# ATX_PSU_Breakout_Mini.net
KiCad netlist of a schematic drawn in EAGLE
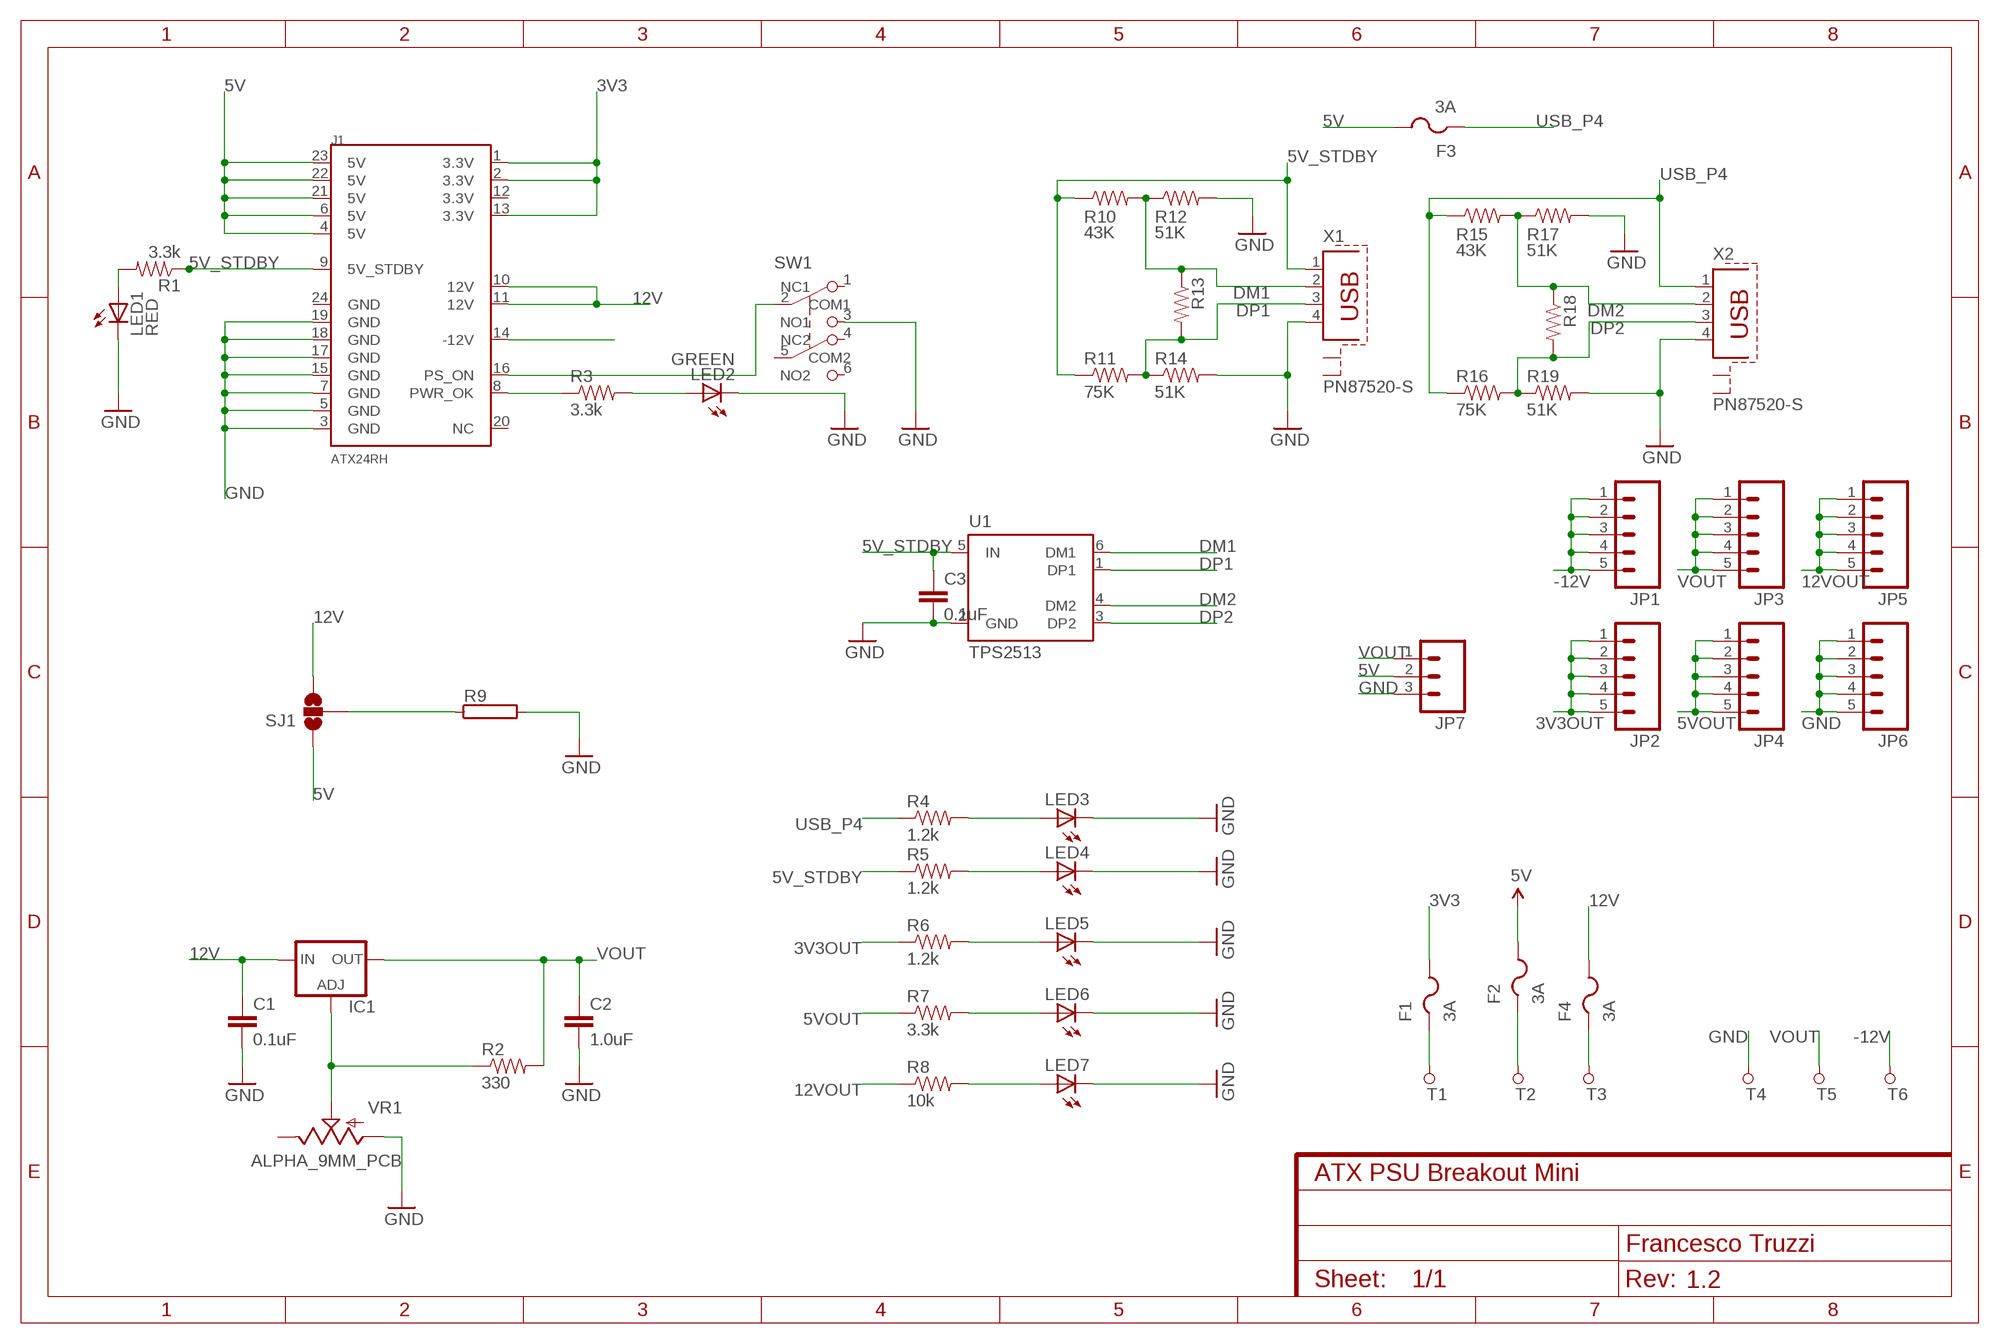
[diagram p0: schematic, sheet 1]

(export (version "E")
  (design (tool "Eeschema 10.0.6"))
  (components
    (comp (ref "C1")
      (value "0.1uF")
      (footprint "eagle-import:0805")
      (libsource (lib "eagle-import") (part "1.0UF-25V-+80/-20(0805)"))
    )
    (comp (ref "C2")
      (value "1.0uF")
      (footprint "eagle-import:0805")
      (libsource (lib "eagle-import") (part "1.0UF-25V-+80/-20(0805)"))
    )
    (comp (ref "C3")
      (value "0.1uF")
      (footprint "eagle-import:0805")
      (libsource (lib "eagle-import") (part "1.0UF-25V-+80/-20(0805)"))
    )
    (comp (ref "F1")
      (value "3A")
      (footprint "eagle-import:1812")
      (libsource (lib "eagle-import") (part "PTCFUSE-1812"))
    )
    (comp (ref "F2")
      (value "3A")
      (footprint "eagle-import:1812")
      (libsource (lib "eagle-import") (part "PTCFUSE-1812"))
    )
    (comp (ref "F3")
      (value "3A")
      (footprint "eagle-import:1812")
      (libsource (lib "eagle-import") (part "PTCFUSE-1812"))
    )
    (comp (ref "F4")
      (value "3A")
      (footprint "eagle-import:1812")
      (libsource (lib "eagle-import") (part "PTCFUSE-1812"))
    )
    (comp (ref "IC1")
      (value "LM317TL")
      (footprint "eagle-import:317TL")
      (libsource (lib "eagle-import") (part "LM317TL"))
    )
    (comp (ref "J1")
      (value "ATX24RH")
      (footprint "eagle-import:ATX24_RIGHT_ANGLE")
      (libsource (lib "eagle-import") (part "ATX24RH"))
    )
    (comp (ref "JP1")
      (value "M05PTH")
      (footprint "eagle-import:1X05")
      (libsource (lib "eagle-import") (part "M05PTH"))
    )
    (comp (ref "JP2")
      (value "M05PTH")
      (footprint "eagle-import:1X05")
      (libsource (lib "eagle-import") (part "M05PTH"))
    )
    (comp (ref "JP3")
      (value "M05PTH")
      (footprint "eagle-import:1X05")
      (libsource (lib "eagle-import") (part "M05PTH"))
    )
    (comp (ref "JP4")
      (value "M05PTH")
      (footprint "eagle-import:1X05")
      (libsource (lib "eagle-import") (part "M05PTH"))
    )
    (comp (ref "JP5")
      (value "M05PTH")
      (footprint "eagle-import:1X05")
      (libsource (lib "eagle-import") (part "M05PTH"))
    )
    (comp (ref "JP6")
      (value "M05PTH")
      (footprint "eagle-import:1X05")
      (libsource (lib "eagle-import") (part "M05PTH"))
    )
    (comp (ref "JP7")
      (value "M03LOCK")
      (footprint "eagle-import:1X03_LOCK")
      (libsource (lib "eagle-import") (part "M03LOCK"))
    )
    (comp (ref "LED1")
      (value "RED")
      (footprint "eagle-import:CHIPLED_0805")
      (libsource (lib "eagle-import") (part "LEDCHIPLED_0805"))
    )
    (comp (ref "LED2")
      (value "GREEN")
      (footprint "eagle-import:CHIPLED_0805")
      (libsource (lib "eagle-import") (part "LEDCHIPLED_0805"))
    )
    (comp (ref "LED3")
      (value "LEDCHIPLED_0805")
      (footprint "eagle-import:CHIPLED_0805")
      (libsource (lib "eagle-import") (part "LEDCHIPLED_0805"))
    )
    (comp (ref "LED4")
      (value "LEDCHIPLED_0805")
      (footprint "eagle-import:CHIPLED_0805")
      (libsource (lib "eagle-import") (part "LEDCHIPLED_0805"))
    )
    (comp (ref "LED5")
      (value "LEDCHIPLED_0805")
      (footprint "eagle-import:CHIPLED_0805")
      (libsource (lib "eagle-import") (part "LEDCHIPLED_0805"))
    )
    (comp (ref "LED6")
      (value "LEDCHIPLED_0805")
      (footprint "eagle-import:CHIPLED_0805")
      (libsource (lib "eagle-import") (part "LEDCHIPLED_0805"))
    )
    (comp (ref "LED7")
      (value "LEDCHIPLED_0805")
      (footprint "eagle-import:CHIPLED_0805")
      (libsource (lib "eagle-import") (part "LEDCHIPLED_0805"))
    )
    (comp (ref "R1")
      (value "3.3k")
      (footprint "eagle-import:0805")
      (libsource (lib "eagle-import") (part "RESISTOR0805-RES"))
    )
    (comp (ref "R2")
      (value "330")
      (footprint "eagle-import:0805")
      (libsource (lib "eagle-import") (part "RESISTOR0805-RES"))
    )
    (comp (ref "R3")
      (value "3.3k")
      (footprint "eagle-import:0805")
      (libsource (lib "eagle-import") (part "RESISTOR0805-RES"))
    )
    (comp (ref "R4")
      (value "1.2k")
      (footprint "eagle-import:0805")
      (libsource (lib "eagle-import") (part "RESISTOR0805-RES"))
    )
    (comp (ref "R5")
      (value "1.2k")
      (footprint "eagle-import:0805")
      (libsource (lib "eagle-import") (part "RESISTOR0805-RES"))
    )
    (comp (ref "R6")
      (value "1.2k")
      (footprint "eagle-import:0805")
      (libsource (lib "eagle-import") (part "RESISTOR0805-RES"))
    )
    (comp (ref "R7")
      (value "3.3k")
      (footprint "eagle-import:0805")
      (libsource (lib "eagle-import") (part "RESISTOR0805-RES"))
    )
    (comp (ref "R8")
      (value "10k")
      (footprint "eagle-import:0805")
      (libsource (lib "eagle-import") (part "RESISTOR0805-RES"))
    )
    (comp (ref "R9")
      (value "RKH214-8")
      (footprint "eagle-import:KH214-8")
      (libsource (lib "eagle-import") (part "RKH214-8"))
    )
    (comp (ref "R10")
      (value "43K")
      (footprint "eagle-import:0805")
      (libsource (lib "eagle-import") (part "RESISTOR0805-RES"))
    )
    (comp (ref "R11")
      (value "75K")
      (footprint "eagle-import:0805")
      (libsource (lib "eagle-import") (part "RESISTOR0805-RES"))
    )
    (comp (ref "R12")
      (value "51K")
      (footprint "eagle-import:0805")
      (libsource (lib "eagle-import") (part "RESISTOR0805-RES"))
    )
    (comp (ref "R13")
      (value "RESISTOR0805-RES")
      (footprint "eagle-import:0805")
      (libsource (lib "eagle-import") (part "RESISTOR0805-RES"))
    )
    (comp (ref "R14")
      (value "51K")
      (footprint "eagle-import:0805")
      (libsource (lib "eagle-import") (part "RESISTOR0805-RES"))
    )
    (comp (ref "R15")
      (value "43K")
      (footprint "eagle-import:0805")
      (libsource (lib "eagle-import") (part "RESISTOR0805-RES"))
    )
    (comp (ref "R16")
      (value "75K")
      (footprint "eagle-import:0805")
      (libsource (lib "eagle-import") (part "RESISTOR0805-RES"))
    )
    (comp (ref "R17")
      (value "51K")
      (footprint "eagle-import:0805")
      (libsource (lib "eagle-import") (part "RESISTOR0805-RES"))
    )
    (comp (ref "R18")
      (value "RESISTOR0805-RES")
      (footprint "eagle-import:0805")
      (libsource (lib "eagle-import") (part "RESISTOR0805-RES"))
    )
    (comp (ref "R19")
      (value "51K")
      (footprint "eagle-import:0805")
      (libsource (lib "eagle-import") (part "RESISTOR0805-RES"))
    )
    (comp (ref "SJ1")
      (value "SOLDERJUMPER_2WAYS")
      (footprint "eagle-import:SJ_3")
      (libsource (lib "eagle-import") (part "SOLDERJUMPER_2WAYS"))
    )
    (comp (ref "SW1")
      (value "SW_PUSH_DPDT")
      (footprint "eagle-import:SW_PUSH_BUTTON_MINI")
      (libsource (lib "eagle-import") (part "SW_PUSH_DPDT"))
    )
    (comp (ref "T1")
      (value "3V3")
      (footprint "eagle-import:PAD_ROUND_4.1MM")
      (libsource (lib "eagle-import") (part "PAD_TERMINAL-4.1MMROUND"))
    )
    (comp (ref "T2")
      (value "5V")
      (footprint "eagle-import:PAD_ROUND_4.1MM")
      (libsource (lib "eagle-import") (part "PAD_TERMINAL-4.1MMROUND"))
    )
    (comp (ref "T3")
      (value "12V")
      (footprint "eagle-import:PAD_ROUND_4.1MM")
      (libsource (lib "eagle-import") (part "PAD_TERMINAL-4.1MMROUND"))
    )
    (comp (ref "T4")
      (value "GND")
      (footprint "eagle-import:PAD_ROUND_4.1MM")
      (libsource (lib "eagle-import") (part "PAD_TERMINAL-4.1MMROUND"))
    )
    (comp (ref "T5")
      (value "ADJ")
      (footprint "eagle-import:PAD_ROUND_4.1MM")
      (libsource (lib "eagle-import") (part "PAD_TERMINAL-4.1MMROUND"))
    )
    (comp (ref "T6")
      (value "-12V")
      (footprint "eagle-import:PAD_ROUND_4.1MM")
      (libsource (lib "eagle-import") (part "PAD_TERMINAL-4.1MMROUND"))
    )
    (comp (ref "U1")
      (value "TPS2513")
      (footprint "eagle-import:SOT23-6")
      (libsource (lib "eagle-import") (part "TPS2513"))
    )
    (comp (ref "VR1")
      (value "ALPHA_9MM_PCB")
      (footprint "eagle-import:ALPHA_9MM_PCB")
      (libsource (lib "eagle-import") (part "ALPHA_9MM_PCB"))
    )
    (comp (ref "X1")
      (value "PN87520-S")
      (footprint "eagle-import:PN87520-S")
      (libsource (lib "eagle-import") (part "PN87520-S"))
    )
    (comp (ref "X2")
      (value "PN87520-S")
      (footprint "eagle-import:PN87520-S")
      (libsource (lib "eagle-import") (part "PN87520-S"))
    )
  )
  (nets
    (net (code "1") (name "/-12V") (class "Default")
      (node (ref "J1") (pin "14") (pinfunction "-12V_14") (pintype "bidirectional"))
      (node (ref "JP1") (pin "1") (pinfunction "1_1") (pintype "passive"))
      (node (ref "JP1") (pin "2") (pinfunction "2_2") (pintype "passive"))
      (node (ref "JP1") (pin "3") (pinfunction "3_3") (pintype "passive"))
      (node (ref "JP1") (pin "4") (pinfunction "4_4") (pintype "passive"))
      (node (ref "JP1") (pin "5") (pinfunction "5_5") (pintype "passive"))
      (node (ref "T6") (pin "P") (pinfunction "P_P") (pintype "passive"))
    )
    (net (code "2") (name "/3V3") (class "Default")
      (node (ref "F1") (pin "2") (pinfunction "2_2") (pintype "passive"))
      (node (ref "J1") (pin "1") (pinfunction "3.3V_1") (pintype "bidirectional"))
      (node (ref "J1") (pin "13") (pinfunction "3.3V_13") (pintype "bidirectional"))
      (node (ref "J1") (pin "2") (pinfunction "3.3V_2") (pintype "bidirectional"))
    )
    (net (code "3") (name "/3V3OUT") (class "Default")
      (node (ref "F1") (pin "1") (pinfunction "1_1") (pintype "passive"))
      (node (ref "JP2") (pin "1") (pinfunction "1_1") (pintype "passive"))
      (node (ref "JP2") (pin "2") (pinfunction "2_2") (pintype "passive"))
      (node (ref "JP2") (pin "3") (pinfunction "3_3") (pintype "passive"))
      (node (ref "JP2") (pin "4") (pinfunction "4_4") (pintype "passive"))
      (node (ref "JP2") (pin "5") (pinfunction "5_5") (pintype "passive"))
      (node (ref "R6") (pin "1") (pinfunction "1_1") (pintype "passive"))
      (node (ref "T1") (pin "P") (pinfunction "P_P") (pintype "passive"))
    )
    (net (code "4") (name "/5VOUT") (class "Default")
      (node (ref "F2") (pin "1") (pinfunction "1_1") (pintype "passive"))
      (node (ref "JP4") (pin "1") (pinfunction "1_1") (pintype "passive"))
      (node (ref "JP4") (pin "2") (pinfunction "2_2") (pintype "passive"))
      (node (ref "JP4") (pin "3") (pinfunction "3_3") (pintype "passive"))
      (node (ref "JP4") (pin "4") (pinfunction "4_4") (pintype "passive"))
      (node (ref "JP4") (pin "5") (pinfunction "5_5") (pintype "passive"))
      (node (ref "R7") (pin "1") (pinfunction "1_1") (pintype "passive"))
      (node (ref "T2") (pin "P") (pinfunction "P_P") (pintype "passive"))
    )
    (net (code "5") (name "/5V_STDBY") (class "Default")
      (node (ref "C3") (pin "1") (pinfunction "1_1") (pintype "passive"))
      (node (ref "J1") (pin "9") (pinfunction "5V_STDBY_9") (pintype "bidirectional"))
      (node (ref "R1") (pin "1") (pinfunction "1_1") (pintype "passive"))
      (node (ref "R10") (pin "1") (pinfunction "1_1") (pintype "passive"))
      (node (ref "R11") (pin "1") (pinfunction "1_1") (pintype "passive"))
      (node (ref "R5") (pin "1") (pinfunction "1_1") (pintype "passive"))
      (node (ref "U1") (pin "5") (pinfunction "IN_5") (pintype "power_in"))
      (node (ref "X1") (pin "1") (pinfunction "1_1") (pintype "passive"))
    )
    (net (code "6") (name "/12V") (class "Default")
      (node (ref "C1") (pin "1") (pinfunction "1_1") (pintype "passive"))
      (node (ref "F4") (pin "2") (pinfunction "2_2") (pintype "passive"))
      (node (ref "IC1") (pin "3") (pinfunction "IN_3") (pintype "input"))
      (node (ref "J1") (pin "10") (pinfunction "12V_10") (pintype "bidirectional"))
      (node (ref "J1") (pin "11") (pinfunction "12V_11") (pintype "bidirectional"))
      (node (ref "SJ1") (pin "3") (pinfunction "3_3") (pintype "passive"))
    )
    (net (code "7") (name "/12VOUT") (class "Default")
      (node (ref "F4") (pin "1") (pinfunction "1_1") (pintype "passive"))
      (node (ref "JP5") (pin "1") (pinfunction "1_1") (pintype "passive"))
      (node (ref "JP5") (pin "2") (pinfunction "2_2") (pintype "passive"))
      (node (ref "JP5") (pin "3") (pinfunction "3_3") (pintype "passive"))
      (node (ref "JP5") (pin "4") (pinfunction "4_4") (pintype "passive"))
      (node (ref "JP5") (pin "5") (pinfunction "5_5") (pintype "passive"))
      (node (ref "R8") (pin "1") (pinfunction "1_1") (pintype "passive"))
      (node (ref "T3") (pin "P") (pinfunction "P_P") (pintype "passive"))
    )
    (net (code "8") (name "/DM1") (class "Default")
      (node (ref "R10") (pin "2") (pinfunction "2_2") (pintype "passive"))
      (node (ref "R12") (pin "1") (pinfunction "1_1") (pintype "passive"))
      (node (ref "R13") (pin "1") (pinfunction "1_1") (pintype "passive"))
      (node (ref "U1") (pin "6") (pinfunction "DM1_6") (pintype "output"))
      (node (ref "X1") (pin "2") (pinfunction "2_2") (pintype "passive"))
    )
    (net (code "9") (name "/DM2") (class "Default")
      (node (ref "R15") (pin "2") (pinfunction "2_2") (pintype "passive"))
      (node (ref "R17") (pin "1") (pinfunction "1_1") (pintype "passive"))
      (node (ref "R18") (pin "1") (pinfunction "1_1") (pintype "passive"))
      (node (ref "U1") (pin "4") (pinfunction "DM2_4") (pintype "bidirectional"))
      (node (ref "X2") (pin "2") (pinfunction "2_2") (pintype "passive"))
    )
    (net (code "10") (name "/DP1") (class "Default")
      (node (ref "R11") (pin "2") (pinfunction "2_2") (pintype "passive"))
      (node (ref "R13") (pin "2") (pinfunction "2_2") (pintype "passive"))
      (node (ref "R14") (pin "1") (pinfunction "1_1") (pintype "passive"))
      (node (ref "U1") (pin "1") (pinfunction "DP1_1") (pintype "output"))
      (node (ref "X1") (pin "3") (pinfunction "3_3") (pintype "passive"))
    )
    (net (code "11") (name "/DP2") (class "Default")
      (node (ref "R16") (pin "2") (pinfunction "2_2") (pintype "passive"))
      (node (ref "R18") (pin "2") (pinfunction "2_2") (pintype "passive"))
      (node (ref "R19") (pin "1") (pinfunction "1_1") (pintype "passive"))
      (node (ref "U1") (pin "3") (pinfunction "DP2_3") (pintype "bidirectional"))
      (node (ref "X2") (pin "3") (pinfunction "3_3") (pintype "passive"))
    )
    (net (code "12") (name "/USB_P4") (class "Default")
      (node (ref "F3") (pin "1") (pinfunction "1_1") (pintype "passive"))
      (node (ref "R15") (pin "1") (pinfunction "1_1") (pintype "passive"))
      (node (ref "R16") (pin "1") (pinfunction "1_1") (pintype "passive"))
      (node (ref "R4") (pin "1") (pinfunction "1_1") (pintype "passive"))
      (node (ref "X2") (pin "1") (pinfunction "1_1") (pintype "passive"))
    )
    (net (code "13") (name "/VOUT") (class "Default")
      (node (ref "C2") (pin "1") (pinfunction "1_1") (pintype "passive"))
      (node (ref "IC1") (pin "2") (pinfunction "OUT_2") (pintype "passive"))
      (node (ref "JP3") (pin "1") (pinfunction "1_1") (pintype "passive"))
      (node (ref "JP3") (pin "2") (pinfunction "2_2") (pintype "passive"))
      (node (ref "JP3") (pin "3") (pinfunction "3_3") (pintype "passive"))
      (node (ref "JP3") (pin "4") (pinfunction "4_4") (pintype "passive"))
      (node (ref "JP3") (pin "5") (pinfunction "5_5") (pintype "passive"))
      (node (ref "JP7") (pin "1") (pinfunction "1_1") (pintype "passive"))
      (node (ref "R2") (pin "2") (pinfunction "2_2") (pintype "passive"))
      (node (ref "T5") (pin "P") (pinfunction "P_P") (pintype "passive"))
    )
    (net (code "14") (name "5V") (class "Default")
      (node (ref "F2") (pin "2") (pinfunction "2_2") (pintype "passive"))
      (node (ref "F3") (pin "2") (pinfunction "2_2") (pintype "passive"))
      (node (ref "J1") (pin "21") (pinfunction "5V_21") (pintype "bidirectional"))
      (node (ref "J1") (pin "22") (pinfunction "5V_22") (pintype "bidirectional"))
      (node (ref "J1") (pin "23") (pinfunction "5V_23") (pintype "bidirectional"))
      (node (ref "J1") (pin "4") (pinfunction "5V_4") (pintype "bidirectional"))
      (node (ref "J1") (pin "6") (pinfunction "5V_6") (pintype "bidirectional"))
      (node (ref "JP7") (pin "2") (pinfunction "2_2") (pintype "passive"))
      (node (ref "SJ1") (pin "1") (pinfunction "1_1") (pintype "passive"))
    )
    (net (code "15") (name "GND") (class "Default")
      (node (ref "C1") (pin "2") (pinfunction "2_2") (pintype "passive"))
      (node (ref "C2") (pin "2") (pinfunction "2_2") (pintype "passive"))
      (node (ref "C3") (pin "2") (pinfunction "2_2") (pintype "passive"))
      (node (ref "J1") (pin "15") (pinfunction "GND_15") (pintype "bidirectional"))
      (node (ref "J1") (pin "17") (pinfunction "GND_17") (pintype "bidirectional"))
      (node (ref "J1") (pin "18") (pinfunction "GND_18") (pintype "bidirectional"))
      (node (ref "J1") (pin "19") (pinfunction "GND_19") (pintype "bidirectional"))
      (node (ref "J1") (pin "3") (pinfunction "GND_3") (pintype "bidirectional"))
      (node (ref "J1") (pin "5") (pinfunction "GND_5") (pintype "bidirectional"))
      (node (ref "J1") (pin "7") (pinfunction "GND_7") (pintype "bidirectional"))
      (node (ref "JP6") (pin "1") (pinfunction "1_1") (pintype "passive"))
      (node (ref "JP6") (pin "2") (pinfunction "2_2") (pintype "passive"))
      (node (ref "JP6") (pin "3") (pinfunction "3_3") (pintype "passive"))
      (node (ref "JP6") (pin "4") (pinfunction "4_4") (pintype "passive"))
      (node (ref "JP6") (pin "5") (pinfunction "5_5") (pintype "passive"))
      (node (ref "JP7") (pin "3") (pinfunction "3_3") (pintype "passive"))
      (node (ref "LED1") (pin "C") (pinfunction "C_C") (pintype "passive"))
      (node (ref "LED2") (pin "C") (pinfunction "C_C") (pintype "passive"))
      (node (ref "LED3") (pin "C") (pinfunction "C_C") (pintype "passive"))
      (node (ref "LED4") (pin "C") (pinfunction "C_C") (pintype "passive"))
      (node (ref "LED5") (pin "C") (pinfunction "C_C") (pintype "passive"))
      (node (ref "LED6") (pin "C") (pinfunction "C_C") (pintype "passive"))
      (node (ref "LED7") (pin "C") (pinfunction "C_C") (pintype "passive"))
      (node (ref "R12") (pin "2") (pinfunction "2_2") (pintype "passive"))
      (node (ref "R14") (pin "2") (pinfunction "2_2") (pintype "passive"))
      (node (ref "R17") (pin "2") (pinfunction "2_2") (pintype "passive"))
      (node (ref "R19") (pin "2") (pinfunction "2_2") (pintype "passive"))
      (node (ref "R9") (pin "2") (pinfunction "2_2") (pintype "passive"))
      (node (ref "SW1") (pin "3") (pinfunction "NO1_3") (pintype "passive"))
      (node (ref "T4") (pin "P") (pinfunction "P_P") (pintype "passive"))
      (node (ref "U1") (pin "2") (pinfunction "GND_2") (pintype "power_in"))
      (node (ref "VR1") (pin "1") (pinfunction "A_1") (pintype "passive"))
      (node (ref "X1") (pin "4") (pinfunction "4_4") (pintype "passive"))
      (node (ref "X2") (pin "4") (pinfunction "4_4") (pintype "passive"))
    )
    (net (code "16") (name "Net-(IC1-ADJ)") (class "Default")
      (node (ref "IC1") (pin "1") (pinfunction "ADJ_1") (pintype "input"))
      (node (ref "R2") (pin "1") (pinfunction "1_1") (pintype "passive"))
      (node (ref "VR1") (pin "2") (pinfunction "S_2") (pintype "passive"))
    )
    (net (code "17") (name "Net-(J1-PS_ON)") (class "Default")
      (node (ref "J1") (pin "16") (pinfunction "PS_ON_16") (pintype "bidirectional"))
      (node (ref "SW1") (pin "2") (pinfunction "COM1_2") (pintype "passive"))
    )
    (net (code "18") (name "Net-(J1-PWR_OK)") (class "Default")
      (node (ref "J1") (pin "8") (pinfunction "PWR_OK_8") (pintype "bidirectional"))
      (node (ref "R3") (pin "1") (pinfunction "1_1") (pintype "passive"))
    )
    (net (code "19") (name "Net-(LED1-PadA)") (class "Default")
      (node (ref "LED1") (pin "A") (pinfunction "A_A") (pintype "passive"))
      (node (ref "R1") (pin "2") (pinfunction "2_2") (pintype "passive"))
    )
    (net (code "20") (name "Net-(LED2-PadA)") (class "Default")
      (node (ref "LED2") (pin "A") (pinfunction "A_A") (pintype "passive"))
      (node (ref "R3") (pin "2") (pinfunction "2_2") (pintype "passive"))
    )
    (net (code "21") (name "Net-(LED3-PadA)") (class "Default")
      (node (ref "LED3") (pin "A") (pinfunction "A_A") (pintype "passive"))
      (node (ref "R4") (pin "2") (pinfunction "2_2") (pintype "passive"))
    )
    (net (code "22") (name "Net-(LED4-PadA)") (class "Default")
      (node (ref "LED4") (pin "A") (pinfunction "A_A") (pintype "passive"))
      (node (ref "R5") (pin "2") (pinfunction "2_2") (pintype "passive"))
    )
    (net (code "23") (name "Net-(LED5-PadA)") (class "Default")
      (node (ref "LED5") (pin "A") (pinfunction "A_A") (pintype "passive"))
      (node (ref "R6") (pin "2") (pinfunction "2_2") (pintype "passive"))
    )
    (net (code "24") (name "Net-(LED6-PadA)") (class "Default")
      (node (ref "LED6") (pin "A") (pinfunction "A_A") (pintype "passive"))
      (node (ref "R7") (pin "2") (pinfunction "2_2") (pintype "passive"))
    )
    (net (code "25") (name "Net-(LED7-PadA)") (class "Default")
      (node (ref "LED7") (pin "A") (pinfunction "A_A") (pintype "passive"))
      (node (ref "R8") (pin "2") (pinfunction "2_2") (pintype "passive"))
    )
    (net (code "26") (name "Net-(R9-Pad1)") (class "Default")
      (node (ref "R9") (pin "1") (pinfunction "1_1") (pintype "passive"))
      (node (ref "SJ1") (pin "2") (pinfunction "2_2") (pintype "passive"))
    )
    (net (code "27") (name "unconnected-(J1-3.3V-Pad12)") (class "Default")
      (node (ref "J1") (pin "12") (pinfunction "3.3V_12") (pintype "bidirectional"))
    )
    (net (code "28") (name "unconnected-(J1-GND-Pad24)") (class "Default")
      (node (ref "J1") (pin "24") (pinfunction "GND_24") (pintype "bidirectional"))
    )
    (net (code "29") (name "unconnected-(J1-NC-Pad20)") (class "Default")
      (node (ref "J1") (pin "20") (pinfunction "NC_20") (pintype "bidirectional"))
    )
    (net (code "30") (name "unconnected-(SW1-COM2-Pad5)") (class "Default")
      (node (ref "SW1") (pin "5") (pinfunction "COM2_5") (pintype "passive"))
    )
    (net (code "31") (name "unconnected-(SW1-NC1-Pad1)") (class "Default")
      (node (ref "SW1") (pin "1") (pinfunction "NC1_1") (pintype "passive"))
    )
    (net (code "32") (name "unconnected-(SW1-NC2-Pad4)") (class "Default")
      (node (ref "SW1") (pin "4") (pinfunction "NC2_4") (pintype "passive"))
    )
    (net (code "33") (name "unconnected-(SW1-NO2-Pad6)") (class "Default")
      (node (ref "SW1") (pin "6") (pinfunction "NO2_6") (pintype "passive"))
    )
    (net (code "34") (name "unconnected-(VR1-E-Pad3)") (class "Default")
      (node (ref "VR1") (pin "3") (pinfunction "E_3") (pintype "passive"))
    )
    (net (code "35") (name "unconnected-(X1-PadS1)") (class "Default")
      (node (ref "X1") (pin "S1") (pinfunction "S1_S1") (pintype "passive"))
    )
    (net (code "36") (name "unconnected-(X1-PadS2)") (class "Default")
      (node (ref "X1") (pin "S2") (pinfunction "S2_S2") (pintype "passive"))
    )
    (net (code "37") (name "unconnected-(X2-PadS1)") (class "Default")
      (node (ref "X2") (pin "S1") (pinfunction "S1_S1") (pintype "passive"))
    )
    (net (code "38") (name "unconnected-(X2-PadS2)") (class "Default")
      (node (ref "X2") (pin "S2") (pinfunction "S2_S2") (pintype "passive"))
    )
  )
)
